# Infrared.net
KiCad netlist of a schematic drawn in Altium Designer
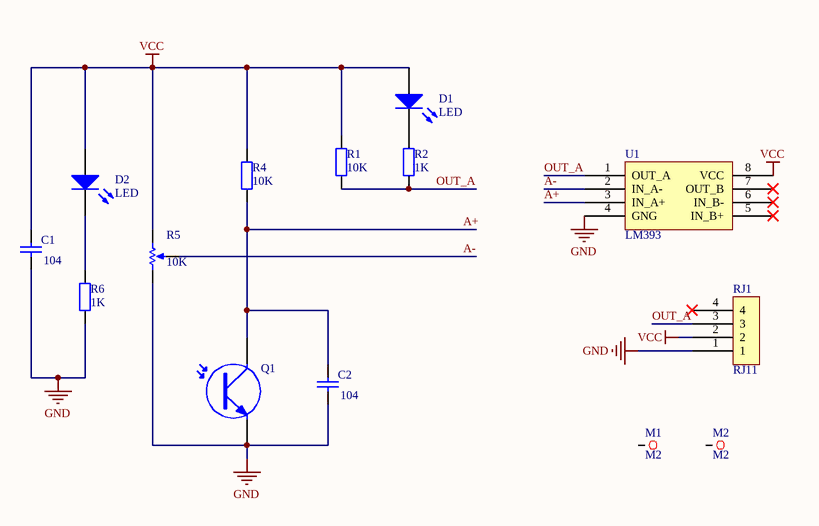
[diagram p0: Infrared.SchDoc]

(export (version "E")
  (design (tool "Eeschema 10.0.6"))
  (components
    (comp (ref "C1")
      (value "104")
      (footprint "0603_C")
      (description "Capacitor")
      (fields (field (name "Comment") "Cap") (field (name "PUBLISHER") "Altium Limited"))
      (libsource (lib "Miscellaneous Devices") (part "Cap"))
    )
    (comp (ref "C2")
      (value "104")
      (footprint "0603_C")
      (description "Capacitor")
      (fields (field (name "Comment") "Cap") (field (name "PUBLISHER") "Altium Limited"))
      (libsource (lib "Miscellaneous Devices") (part "Cap"))
    )
    (comp (ref "D1")
      (value "LED")
      (footprint "0805")
      (description "Typical RED GaAs LED")
      (fields (field (name "PUBLISHER") "Altium Limited"))
      (libsource (lib "Miscellaneous Devices") (part "LED1"))
    )
    (comp (ref "D2")
      (value "LED")
      (footprint "0805")
      (description "Typical RED GaAs LED")
      (fields (field (name "PUBLISHER") "Altium Limited"))
      (libsource (lib "Miscellaneous Devices") (part "LED1"))
    )
    (comp (ref "M1") (value "M2") (footprint "M2") (libsource (lib "QQW-1.SCHLIB") (part "M3")))
    (comp (ref "M2") (value "M2") (footprint "M2") (libsource (lib "QQW-1.SCHLIB") (part "M3")))
    (comp (ref "Q1")
      (value "Photo NPN")
      (footprint "红外")
      (description "NPN Phototransistor")
      (fields (field (name "PUBLISHER") "Altium Limited"))
      (libsource (lib "Miscellaneous Devices") (part "Photo NPN"))
    )
    (comp (ref "R1")
      (value "10K")
      (footprint "0603_R")
      (description "Resistor")
      (fields (field (name "Comment") "Res2") (field (name "PUBLISHER") "Altium Limited"))
      (libsource (lib "Miscellaneous Devices") (part "Res2"))
    )
    (comp (ref "R2")
      (value "1K")
      (footprint "0603_R")
      (description "Resistor")
      (fields (field (name "Comment") "Res2") (field (name "PUBLISHER") "Altium Limited"))
      (libsource (lib "Miscellaneous Devices") (part "Res2"))
    )
    (comp (ref "R4")
      (value "10K")
      (footprint "0603_R")
      (description "Resistor")
      (fields (field (name "Comment") "Res2") (field (name "PUBLISHER") "Altium Limited"))
      (libsource (lib "Miscellaneous Devices") (part "Res2"))
    )
    (comp (ref "R5")
      (value "10K")
      (footprint "电位器")
      (description "Potentiometer")
      (fields (field (name "Comment") "RPot") (field (name "PUBLISHER") "Altium Limited"))
      (libsource (lib "Miscellaneous Devices") (part "RPot"))
    )
    (comp (ref "R6")
      (value "1K")
      (footprint "0603_R")
      (description "Resistor")
      (fields (field (name "Comment") "Res2") (field (name "PUBLISHER") "Altium Limited"))
      (libsource (lib "Miscellaneous Devices") (part "Res2"))
    )
    (comp (ref "RJ1") (value "RJ11") (footprint "RJ11") (libsource (lib "少儿智能车") (part "RJ11")))
    (comp (ref "U1") (value "LM393") (footprint "SO-8") (libsource (lib "Infrared") (part "LM393")))
  )
  (nets
    (net (code "1") (name "/A+") (class "Default")
      (node (ref "C2") (pin "2") (pinfunction "2_2") (pintype "passive"))
      (node (ref "Q1") (pin "2") (pinfunction "C_2") (pintype "passive"))
      (node (ref "R4") (pin "1") (pinfunction "1_1") (pintype "passive"))
      (node (ref "U1") (pin "3") (pinfunction "IN_A+_3") (pintype "passive"))
    )
    (net (code "2") (name "/A-") (class "Default")
      (node (ref "R5") (pin "3") (pinfunction "TAP_3") (pintype "passive"))
      (node (ref "U1") (pin "2") (pinfunction "IN_A-_2") (pintype "passive"))
    )
    (net (code "3") (name "/OUT_A") (class "Default")
      (node (ref "R1") (pin "1") (pinfunction "1_1") (pintype "passive"))
      (node (ref "R2") (pin "1") (pinfunction "1_1") (pintype "passive"))
      (node (ref "RJ1") (pin "3") (pinfunction "3_3") (pintype "passive"))
      (node (ref "U1") (pin "1") (pinfunction "OUT_A_1") (pintype "passive"))
    )
    (net (code "4") (name "GND") (class "Default")
      (node (ref "C1") (pin "1") (pinfunction "1_1") (pintype "passive"))
      (node (ref "C2") (pin "1") (pinfunction "1_1") (pintype "passive"))
      (node (ref "Q1") (pin "1") (pinfunction "E_1") (pintype "passive"))
      (node (ref "R5") (pin "1") (pinfunction "TOP_1") (pintype "passive"))
      (node (ref "R6") (pin "1") (pinfunction "1_1") (pintype "passive"))
      (node (ref "RJ1") (pin "1") (pinfunction "1_1") (pintype "passive"))
      (node (ref "U1") (pin "4") (pinfunction "GNG_4") (pintype "passive"))
    )
    (net (code "5") (name "Net-(D1-K)") (class "Default")
      (node (ref "D1") (pin "2") (pinfunction "K_2") (pintype "passive"))
      (node (ref "R2") (pin "2") (pinfunction "2_2") (pintype "passive"))
    )
    (net (code "6") (name "Net-(D2-K)") (class "Default")
      (node (ref "D2") (pin "2") (pinfunction "K_2") (pintype "passive"))
      (node (ref "R6") (pin "2") (pinfunction "2_2") (pintype "passive"))
    )
    (net (code "7") (name "VCC") (class "Default")
      (node (ref "C1") (pin "2") (pinfunction "2_2") (pintype "passive"))
      (node (ref "D1") (pin "1") (pinfunction "A_1") (pintype "passive"))
      (node (ref "D2") (pin "1") (pinfunction "A_1") (pintype "passive"))
      (node (ref "R1") (pin "2") (pinfunction "2_2") (pintype "passive"))
      (node (ref "R4") (pin "2") (pinfunction "2_2") (pintype "passive"))
      (node (ref "R5") (pin "2") (pinfunction "BOT_2") (pintype "passive"))
      (node (ref "RJ1") (pin "2") (pinfunction "2_2") (pintype "passive"))
      (node (ref "U1") (pin "8") (pinfunction "VCC_8") (pintype "passive"))
    )
    (net (code "8") (name "unconnected-(M1-Pad0)") (class "Default")
      (node (ref "M1") (pin "0") (pinfunction "0_0") (pintype "passive"))
    )
    (net (code "9") (name "unconnected-(M2-Pad0)") (class "Default")
      (node (ref "M2") (pin "0") (pinfunction "0_0") (pintype "passive"))
    )
    (net (code "10") (name "unconnected-(RJ1-Pad4)") (class "Default")
      (node (ref "RJ1") (pin "4") (pinfunction "4_4") (pintype "passive+no_connect"))
    )
    (net (code "11") (name "unconnected-(U1-IN_B+-Pad5)") (class "Default")
      (node (ref "U1") (pin "5") (pinfunction "IN_B+_5") (pintype "passive+no_connect"))
    )
    (net (code "12") (name "unconnected-(U1-IN_B--Pad6)") (class "Default")
      (node (ref "U1") (pin "6") (pinfunction "IN_B-_6") (pintype "passive+no_connect"))
    )
    (net (code "13") (name "unconnected-(U1-OUT_B-Pad7)") (class "Default")
      (node (ref "U1") (pin "7") (pinfunction "OUT_B_7") (pintype "passive+no_connect"))
    )
  )
)
